# BLDC_Motor_Reversal_Rev1.net
KiCad netlist of a schematic drawn in Altium Designer
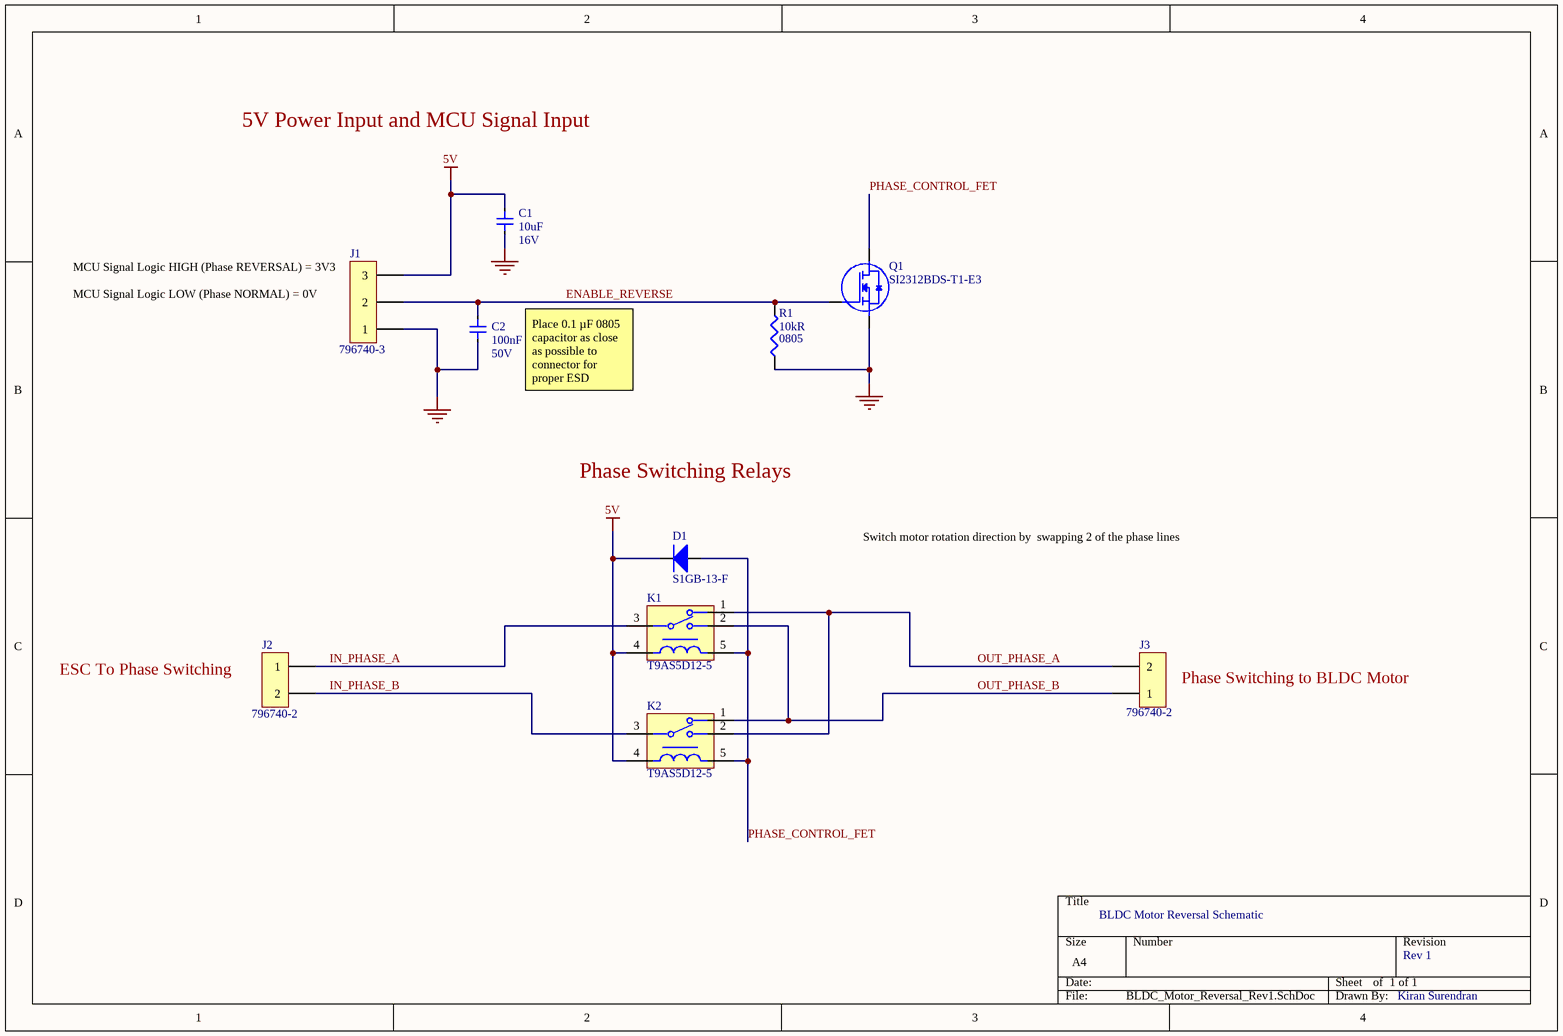
[diagram p0: BLDC_Motor_Reversal_Rev1.SchDoc]

(export (version "E")
  (design (tool "Eeschema 10.0.6"))
  (components
    (comp (ref "C1")
      (value "C0805C106K4PACTU")
      (footprint "C0805C106K4PACTU")
      (description "CERAMIC CAPACITOR, 10UF, 16V, X5R, 10%, 0805")
      (fields (field (name "VOLTAGE RATING") "16V") (field (name "CAPACITANCE") "10uF"))
      (libsource (lib "BLDC_Motor_Lib") (part "C0805C106K4PACTU"))
    )
    (comp (ref "C2")
      (value "C0805C104K5RACTU")
      (footprint "C0805C104K5RACTU")
      (description "Cap Ceramic 0.1uF 50V X7R 10% SMD 2.0 x 1.2 mm 125 C Paper T/R")
      (fields (field (name "VOLTAGE RATING") "50V") (field (name "CAPACITANCE") "100nF"))
      (libsource (lib "BLDC_Motor_Lib") (part "C0805C104K5RACTU"))
    )
    (comp (ref "D1")
      (value "S1GB-13-F")
      (footprint "S1GB-13-F")
      (description "DIODE GEN PURP 400V 1A SMB")
      (libsource (lib "BLDC_Motor_SchLib") (part "S1GB-13-F"))
    )
    (comp (ref "J1")
      (value "796740-3")
      (footprint "796740-3")
      (description "TERM BLK 3P SIDE ENT 6.35MM PCB")
      (libsource (lib "BLDC_Motor_Lib") (part "796740-3"))
    )
    (comp (ref "J2")
      (value "796740-2")
      (footprint "796740-2")
      (description "TERMINAL BLOCK, PLUG, 2POS, 24-10AWG")
      (fields (field (name "MANUFACTURER") "TE Connectivity"))
      (libsource (lib "") (part "796740-2_1"))
    )
    (comp (ref "J3")
      (value "796740-2")
      (footprint "796740-2")
      (description "TERMINAL BLOCK, PLUG, 2POS, 24-10AWG")
      (fields (field (name "MANUFACTURER") "TE Connectivity"))
      (libsource (lib "BLDC_Motor_Lib") (part "796740-2"))
    )
    (comp (ref "K1")
      (value "T9AS5D12-5")
      (footprint "T9AS5D12-5")
      (description "RELAY GEN PURPOSE SPDT 20A 5V")
      (libsource (lib "BLDC_Motor_Lib") (part "T9AS5D12-5"))
    )
    (comp (ref "K2")
      (value "T9AS5D12-5")
      (footprint "T9AS5D12-5")
      (description "RELAY GEN PURPOSE SPDT 20A 5V")
      (libsource (lib "BLDC_Motor_Lib") (part "T9AS5D12-5"))
    )
    (comp (ref "Q1")
      (value "SI2312BDS-T1-E3")
      (footprint "SI2312BDS-T1-E3")
      (description "MOSFET")
      (libsource (lib "BLDC_Motor_Lib") (part "SI2312BDS-T1-E3"))
    )
    (comp (ref "R1")
      (value "RC0805JR-0710KL")
      (footprint "RC0805JR-0710KL")
      (description "Res Thick Film 0805 10K Ohm 5% 1/8W ±100ppm/°C Molded SMD Paper T/R")
      (fields
        (field (name "TOLERANCE") "5%")
        (field (name "PACKAGE") "0805")
        (field (name "RESISTANCE") "10kR")
      )
      (libsource (lib "BLDC_Motor_Lib") (part "RC0805JR-0710KL"))
    )
  )
  (nets
    (net (code "1") (name "/ENABLE_REVERSE") (class "Default")
      (node (ref "C2") (pin "2") (pintype "passive"))
      (node (ref "J1") (pin "2") (pinfunction "2_2") (pintype "passive"))
      (node (ref "Q1") (pin "1") (pinfunction "Gate_1") (pintype "passive"))
      (node (ref "R1") (pin "2") (pintype "passive"))
    )
    (net (code "2") (name "/IN_PHASE_A") (class "Default")
      (node (ref "J2") (pin "1") (pinfunction "1_1") (pintype "passive"))
      (node (ref "K1") (pin "3") (pinfunction "COM_3") (pintype "passive"))
    )
    (net (code "3") (name "/IN_PHASE_B") (class "Default")
      (node (ref "J2") (pin "2") (pinfunction "2_2") (pintype "passive"))
      (node (ref "K2") (pin "3") (pinfunction "COM_3") (pintype "passive"))
    )
    (net (code "4") (name "/OUT_PHASE_A") (class "Default")
      (node (ref "J3") (pin "2") (pinfunction "2_2") (pintype "passive"))
      (node (ref "K1") (pin "1") (pinfunction "NC_1") (pintype "passive"))
      (node (ref "K2") (pin "2") (pinfunction "NO_2") (pintype "passive"))
    )
    (net (code "5") (name "/OUT_PHASE_B") (class "Default")
      (node (ref "J3") (pin "1") (pinfunction "1_1") (pintype "passive"))
      (node (ref "K1") (pin "2") (pinfunction "NO_2") (pintype "passive"))
      (node (ref "K2") (pin "1") (pinfunction "NC_1") (pintype "passive"))
    )
    (net (code "6") (name "/PHASE_CONTROL_FET") (class "Default")
      (node (ref "D1") (pin "2") (pinfunction "+_2") (pintype "passive"))
      (node (ref "K1") (pin "5") (pinfunction "5_5") (pintype "passive"))
      (node (ref "K2") (pin "5") (pinfunction "5_5") (pintype "passive"))
      (node (ref "Q1") (pin "3") (pinfunction "Drain_3") (pintype "passive"))
    )
    (net (code "7") (name "5V") (class "Default")
      (node (ref "C1") (pin "2") (pintype "passive"))
      (node (ref "D1") (pin "1") (pinfunction "-_1") (pintype "passive"))
      (node (ref "J1") (pin "3") (pinfunction "3_3") (pintype "passive"))
      (node (ref "K1") (pin "4") (pinfunction "4_4") (pintype "passive"))
      (node (ref "K2") (pin "4") (pinfunction "4_4") (pintype "passive"))
    )
    (net (code "8") (name "GND") (class "Default")
      (node (ref "C1") (pin "1") (pintype "passive"))
      (node (ref "C2") (pin "1") (pintype "passive"))
      (node (ref "J1") (pin "1") (pinfunction "1_1") (pintype "passive"))
      (node (ref "Q1") (pin "2") (pinfunction "Source_2") (pintype "passive"))
      (node (ref "R1") (pin "1") (pintype "passive"))
    )
  )
)
